# WirelessReceiver.net
KiCad netlist of a schematic drawn in EAGLE
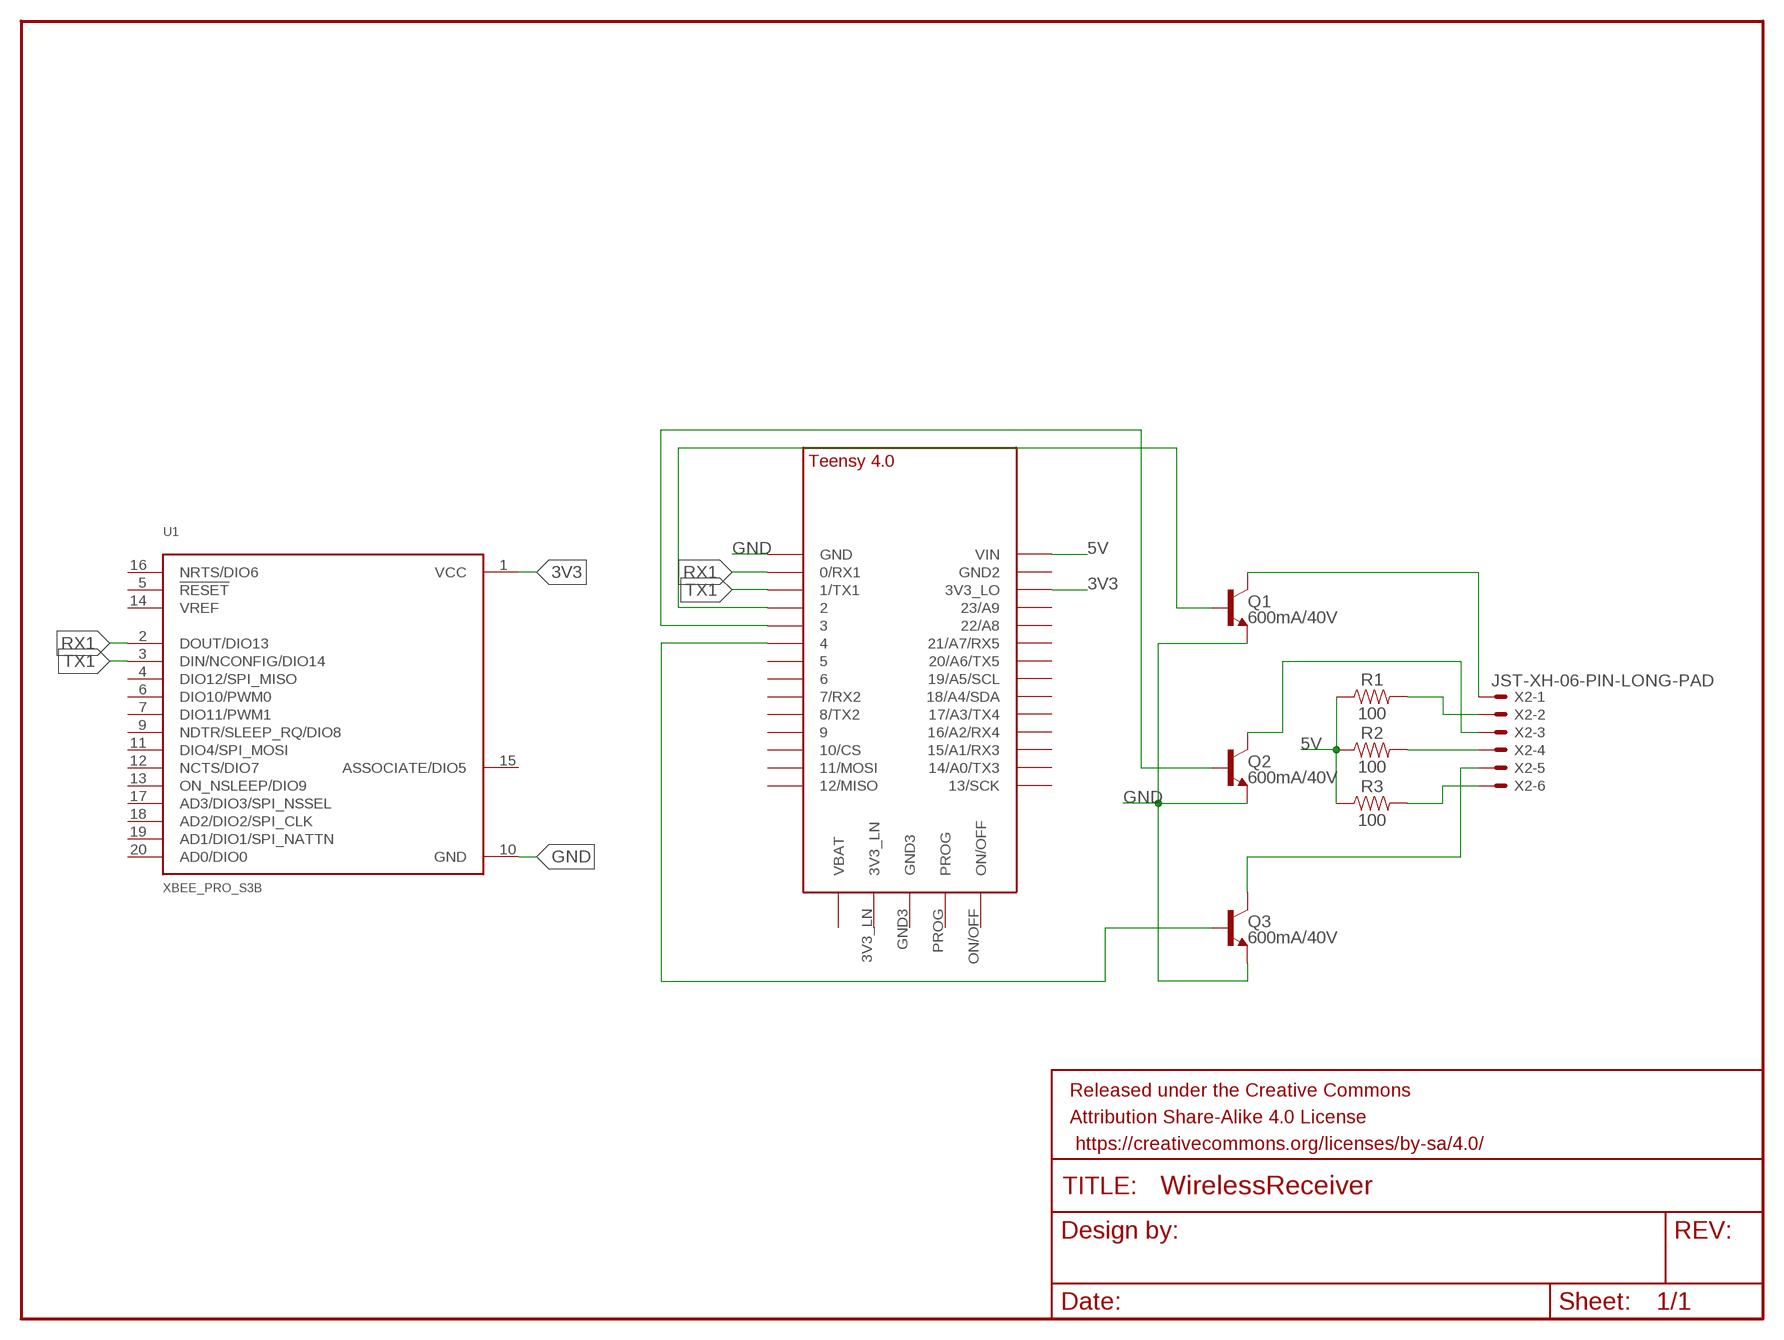
[diagram p0: schematic, sheet 1]

(export (version "E")
  (design (tool "Eeschema 10.0.6"))
  (components
    (comp (ref "FRAME1")
      (value "FRAME-LETTERNO_PACKAGE")
      (footprint "eagle-import:DUMMY")
      (fields (field (name "DESIGNER") "Nobody"))
      (libsource (lib "eagle-import") (part "FRAME-LETTERNO_PACKAGE"))
    )
    (comp (ref "Q1")
      (value "600mA/40V")
      (footprint "eagle-import:SOT23-3")
      (libsource (lib "eagle-import") (part "TRANS_NPN-MMBT2222AL"))
    )
    (comp (ref "Q2")
      (value "600mA/40V")
      (footprint "eagle-import:SOT23-3")
      (libsource (lib "eagle-import") (part "TRANS_NPN-MMBT2222AL"))
    )
    (comp (ref "Q3")
      (value "600mA/40V")
      (footprint "eagle-import:SOT23-3")
      (libsource (lib "eagle-import") (part "TRANS_NPN-MMBT2222AL"))
    )
    (comp (ref "R1")
      (value "100")
      (footprint "eagle-import:AXIAL-0.3")
      (libsource (lib "eagle-import") (part "100OHM-HORIZ-1/4W-1%"))
    )
    (comp (ref "R2")
      (value "100")
      (footprint "eagle-import:AXIAL-0.3")
      (libsource (lib "eagle-import") (part "100OHM-HORIZ-1/4W-1%"))
    )
    (comp (ref "R3")
      (value "100")
      (footprint "eagle-import:AXIAL-0.3")
      (libsource (lib "eagle-import") (part "100OHM-HORIZ-1/4W-1%"))
    )
    (comp (ref "U$1")
      (value "TEENSY_4.0-BASIC")
      (footprint "eagle-import:TEENSY_4.0-BASIC")
      (libsource (lib "eagle-import") (part "TEENSY_4.0-BASIC"))
    )
    (comp (ref "U1")
      (value "XBEE_PRO_S3B")
      (footprint "eagle-import:XBEE_PRO_S3B")
      (fields
        (field (name "DIGI-KEY_PART_NUMBER") "602-1293-ND")
        (field (name "MF") "Digi International")
        (field (name "MP") "XBP9B-XCST-001")
      )
      (libsource (lib "eagle-import") (part "XBEE_PRO_S3B"))
    )
    (comp (ref "X2")
      (value "JST-XH-06-PIN-LONG-PAD")
      (footprint "eagle-import:JST-XH-06-PACKAGE-LONG-PAD")
      (libsource (lib "eagle-import") (part "JST-XH-06-PIN-LONG-PAD"))
    )
  )
  (nets
    (net (code "1") (name "/5V") (class "Default")
      (node (ref "R1") (pin "P$1") (pinfunction "1_P$1") (pintype "passive"))
      (node (ref "R2") (pin "P$1") (pinfunction "1_P$1") (pintype "passive"))
      (node (ref "R3") (pin "P$1") (pinfunction "1_P$1") (pintype "passive"))
      (node (ref "U$1") (pin "VIN") (pinfunction "VIN_VIN") (pintype "bidirectional"))
    )
    (net (code "2") (name "3V3") (class "Default")
      (node (ref "U$1") (pin "3V3_LO") (pinfunction "3V3_LO_3V3_LO") (pintype "bidirectional"))
      (node (ref "U1") (pin "1") (pinfunction "VCC_1") (pintype "power_in"))
    )
    (net (code "3") (name "GND") (class "Default")
      (node (ref "Q1") (pin "2") (pinfunction "E_2") (pintype "passive"))
      (node (ref "Q2") (pin "2") (pinfunction "E_2") (pintype "passive"))
      (node (ref "Q3") (pin "2") (pinfunction "E_2") (pintype "passive"))
      (node (ref "U$1") (pin "GND") (pinfunction "GND_GND") (pintype "bidirectional"))
      (node (ref "U1") (pin "10") (pinfunction "GND_10") (pintype "power_in"))
    )
    (net (code "4") (name "Net-(Q1-B)") (class "Default")
      (node (ref "Q1") (pin "1") (pinfunction "B_1") (pintype "passive"))
      (node (ref "U$1") (pin "2") (pinfunction "2_2") (pintype "bidirectional"))
    )
    (net (code "5") (name "Net-(Q1-C)") (class "Default")
      (node (ref "Q1") (pin "3") (pinfunction "C_3") (pintype "passive"))
      (node (ref "X2") (pin "1") (pinfunction "S_1") (pintype "passive"))
    )
    (net (code "6") (name "Net-(Q2-B)") (class "Default")
      (node (ref "Q2") (pin "1") (pinfunction "B_1") (pintype "passive"))
      (node (ref "U$1") (pin "3/CANTX") (pinfunction "3_3/CANTX") (pintype "bidirectional"))
    )
    (net (code "7") (name "Net-(Q2-C)") (class "Default")
      (node (ref "Q2") (pin "3") (pinfunction "C_3") (pintype "passive"))
      (node (ref "X2") (pin "3") (pinfunction "S_3") (pintype "passive"))
    )
    (net (code "8") (name "Net-(Q3-B)") (class "Default")
      (node (ref "Q3") (pin "1") (pinfunction "B_1") (pintype "passive"))
      (node (ref "U$1") (pin "4/CANRX") (pinfunction "4_4/CANRX") (pintype "bidirectional"))
    )
    (net (code "9") (name "Net-(Q3-C)") (class "Default")
      (node (ref "Q3") (pin "3") (pinfunction "C_3") (pintype "passive"))
      (node (ref "X2") (pin "5") (pinfunction "S_5") (pintype "passive"))
    )
    (net (code "10") (name "Net-(R1-2)") (class "Default")
      (node (ref "R1") (pin "P$2") (pinfunction "2_P$2") (pintype "passive"))
      (node (ref "X2") (pin "2") (pinfunction "S_2") (pintype "passive"))
    )
    (net (code "11") (name "Net-(R2-2)") (class "Default")
      (node (ref "R2") (pin "P$2") (pinfunction "2_P$2") (pintype "passive"))
      (node (ref "X2") (pin "4") (pinfunction "S_4") (pintype "passive"))
    )
    (net (code "12") (name "Net-(R3-2)") (class "Default")
      (node (ref "R3") (pin "P$2") (pinfunction "2_P$2") (pintype "passive"))
      (node (ref "X2") (pin "6") (pinfunction "S_6") (pintype "passive"))
    )
    (net (code "13") (name "RX1") (class "Default")
      (node (ref "U$1") (pin "0/RX") (pinfunction "0/RX1_0/RX") (pintype "bidirectional"))
      (node (ref "U1") (pin "2") (pinfunction "DOUT/DIO13_2") (pintype "bidirectional"))
    )
    (net (code "14") (name "TX1") (class "Default")
      (node (ref "U$1") (pin "1/TX") (pinfunction "1/TX1_1/TX") (pintype "bidirectional"))
      (node (ref "U1") (pin "3") (pinfunction "DIN/NCONFIG/DIO14_3") (pintype "bidirectional"))
    )
    (net (code "15") (name "unconnected-(U$1-7{slash}RX2-Pad7)") (class "Default")
      (node (ref "U$1") (pin "7") (pinfunction "7/RX2_7") (pintype "bidirectional"))
    )
    (net (code "16") (name "unconnected-(U$1-8{slash}TX2-Pad8)") (class "Default")
      (node (ref "U$1") (pin "8") (pinfunction "8/TX2_8") (pintype "bidirectional"))
    )
    (net (code "17") (name "unconnected-(U$1-9-Pad9{slash}CS)") (class "Default")
      (node (ref "U$1") (pin "9/CS") (pinfunction "9_9/CS") (pintype "bidirectional"))
    )
    (net (code "18") (name "unconnected-(U$1-14{slash}A0{slash}TX3-Pad14{slash}A0)") (class "Default")
      (node (ref "U$1") (pin "14/A0") (pinfunction "14/A0/TX3_14/A0") (pintype "bidirectional"))
    )
    (net (code "19") (name "unconnected-(U$1-15{slash}A1{slash}RX3-Pad15{slash}A1)") (class "Default")
      (node (ref "U$1") (pin "15/A1") (pinfunction "15/A1/RX3_15/A1") (pintype "bidirectional"))
    )
    (net (code "20") (name "unconnected-(U$1-16{slash}A2{slash}RX4-Pad16{slash}A2)") (class "Default")
      (node (ref "U$1") (pin "16/A2") (pinfunction "16/A2/RX4_16/A2") (pintype "bidirectional"))
    )
    (net (code "21") (name "unconnected-(U$1-17{slash}A3{slash}TX4-Pad17{slash}A3)") (class "Default")
      (node (ref "U$1") (pin "17/A3") (pinfunction "17/A3/TX4_17/A3") (pintype "bidirectional"))
    )
    (net (code "22") (name "unconnected-(U$1-20{slash}A6{slash}TX5-Pad20{slash}A6)") (class "Default")
      (node (ref "U$1") (pin "20/A6") (pinfunction "20/A6/TX5_20/A6") (pintype "bidirectional"))
    )
    (net (code "23") (name "unconnected-(U$1-21{slash}A7{slash}RX5-Pad21{slash}A7)") (class "Default")
      (node (ref "U$1") (pin "21/A7") (pinfunction "21/A7/RX5_21/A7") (pintype "bidirectional"))
    )
    (net (code "24") (name "unconnected-(U$1-Pad3V3_LN)") (class "Default")
      (node (ref "U$1") (pin "3V3_LN") (pinfunction "3V3_LN_3V3_LN") (pintype "bidirectional"))
    )
    (net (code "25") (name "unconnected-(U$1-Pad5)") (class "Default")
      (node (ref "U$1") (pin "5") (pinfunction "5_5") (pintype "bidirectional"))
    )
    (net (code "26") (name "unconnected-(U$1-Pad6)") (class "Default")
      (node (ref "U$1") (pin "6") (pinfunction "6_6") (pintype "bidirectional"))
    )
    (net (code "27") (name "unconnected-(U$1-Pad10{slash}CS)") (class "Default")
      (node (ref "U$1") (pin "10/CS") (pinfunction "10/CS_10/CS") (pintype "bidirectional"))
    )
    (net (code "28") (name "unconnected-(U$1-Pad11{slash}MOSI)") (class "Default")
      (node (ref "U$1") (pin "11/MOSI") (pinfunction "11/MOSI_11/MOSI") (pintype "bidirectional"))
    )
    (net (code "29") (name "unconnected-(U$1-Pad12{slash}MISO)") (class "Default")
      (node (ref "U$1") (pin "12/MISO") (pinfunction "12/MISO_12/MISO") (pintype "bidirectional"))
    )
    (net (code "30") (name "unconnected-(U$1-Pad13{slash}SCK)") (class "Default")
      (node (ref "U$1") (pin "13/SCK") (pinfunction "13/SCK_13/SCK") (pintype "bidirectional"))
    )
    (net (code "31") (name "unconnected-(U$1-Pad18{slash}A4{slash}SDA)") (class "Default")
      (node (ref "U$1") (pin "18/A4/SDA") (pinfunction "18/A4/SDA_18/A4/SDA") (pintype "bidirectional"))
    )
    (net (code "32") (name "unconnected-(U$1-Pad19{slash}A5{slash}SCL)") (class "Default")
      (node (ref "U$1") (pin "19/A5/SCL") (pinfunction "19/A5/SCL_19/A5/SCL") (pintype "bidirectional"))
    )
    (net (code "33") (name "unconnected-(U$1-Pad22{slash}A8)") (class "Default")
      (node (ref "U$1") (pin "22/A8") (pinfunction "22/A8_22/A8") (pintype "bidirectional"))
    )
    (net (code "34") (name "unconnected-(U$1-Pad23{slash}A9)") (class "Default")
      (node (ref "U$1") (pin "23/A9") (pinfunction "23/A9_23/A9") (pintype "bidirectional"))
    )
    (net (code "35") (name "unconnected-(U$1-PadGND2)") (class "Default")
      (node (ref "U$1") (pin "GND2") (pinfunction "GND2_GND2") (pintype "bidirectional"))
    )
    (net (code "36") (name "unconnected-(U$1-PadGND3)") (class "Default")
      (node (ref "U$1") (pin "GND3") (pinfunction "GND3_GND3") (pintype "bidirectional"))
    )
    (net (code "37") (name "unconnected-(U$1-PadON{slash}OFF)") (class "Default")
      (node (ref "U$1") (pin "ON/OFF") (pinfunction "ON/OFF_ON/OFF") (pintype "bidirectional"))
    )
    (net (code "38") (name "unconnected-(U$1-PadPROG)") (class "Default")
      (node (ref "U$1") (pin "PROG") (pinfunction "PROG_PROG") (pintype "bidirectional"))
    )
    (net (code "39") (name "unconnected-(U$1-VBAT-PadVBAT\\)") (class "Default")
      (node (ref "U$1") (pin "VBAT\\") (pinfunction "VBAT_VBAT\\") (pintype "bidirectional"))
    )
    (net (code "40") (name "unconnected-(U1-AD0{slash}DIO0-Pad20)") (class "Default")
      (node (ref "U1") (pin "20") (pinfunction "AD0/DIO0_20") (pintype "bidirectional"))
    )
    (net (code "41") (name "unconnected-(U1-AD1{slash}DIO1{slash}SPI_NATTN-Pad19)") (class "Default")
      (node (ref "U1") (pin "19") (pinfunction "AD1/DIO1/SPI_NATTN_19") (pintype "bidirectional"))
    )
    (net (code "42") (name "unconnected-(U1-AD2{slash}DIO2{slash}SPI_CLK-Pad18)") (class "Default")
      (node (ref "U1") (pin "18") (pinfunction "AD2/DIO2/SPI_CLK_18") (pintype "bidirectional"))
    )
    (net (code "43") (name "unconnected-(U1-AD3{slash}DIO3{slash}SPI_NSSEL-Pad17)") (class "Default")
      (node (ref "U1") (pin "17") (pinfunction "AD3/DIO3/SPI_NSSEL_17") (pintype "bidirectional"))
    )
    (net (code "44") (name "unconnected-(U1-ASSOCIATE{slash}DIO5-Pad15)") (class "Default")
      (node (ref "U1") (pin "15") (pinfunction "ASSOCIATE/DIO5_15") (pintype "output"))
    )
    (net (code "45") (name "unconnected-(U1-DIO4{slash}SPI_MOSI-Pad11)") (class "Default")
      (node (ref "U1") (pin "11") (pinfunction "DIO4/SPI_MOSI_11") (pintype "bidirectional"))
    )
    (net (code "46") (name "unconnected-(U1-DIO10{slash}PWM0-Pad6)") (class "Default")
      (node (ref "U1") (pin "6") (pinfunction "DIO10/PWM0_6") (pintype "bidirectional"))
    )
    (net (code "47") (name "unconnected-(U1-DIO11{slash}PWM1-Pad7)") (class "Default")
      (node (ref "U1") (pin "7") (pinfunction "DIO11/PWM1_7") (pintype "bidirectional"))
    )
    (net (code "48") (name "unconnected-(U1-DIO12{slash}SPI_MISO-Pad4)") (class "Default")
      (node (ref "U1") (pin "4") (pinfunction "DIO12/SPI_MISO_4") (pintype "bidirectional"))
    )
    (net (code "49") (name "unconnected-(U1-NCTS{slash}DIO7-Pad12)") (class "Default")
      (node (ref "U1") (pin "12") (pinfunction "NCTS/DIO7_12") (pintype "bidirectional"))
    )
    (net (code "50") (name "unconnected-(U1-NDTR{slash}SLEEP_RQ{slash}DIO8-Pad9)") (class "Default")
      (node (ref "U1") (pin "9") (pinfunction "NDTR/SLEEP_RQ/DIO8_9") (pintype "bidirectional"))
    )
    (net (code "51") (name "unconnected-(U1-NRTS{slash}DIO6-Pad16)") (class "Default")
      (node (ref "U1") (pin "16") (pinfunction "NRTS/DIO6_16") (pintype "input"))
    )
    (net (code "52") (name "unconnected-(U1-ON_NSLEEP{slash}DIO9-Pad13)") (class "Default")
      (node (ref "U1") (pin "13") (pinfunction "ON_NSLEEP/DIO9_13") (pintype "bidirectional"))
    )
    (net (code "53") (name "unconnected-(U1-VREF-Pad14)") (class "Default")
      (node (ref "U1") (pin "14") (pinfunction "VREF_14") (pintype "input"))
    )
    (net (code "54") (name "unconnected-(U1-~{RESET}-Pad5)") (class "Default")
      (node (ref "U1") (pin "5") (pinfunction "~{RESET}_5") (pintype "input"))
    )
  )
)
